# RFM69_USB_Gateway_0_92.net
KiCad netlist of a schematic drawn in EAGLE
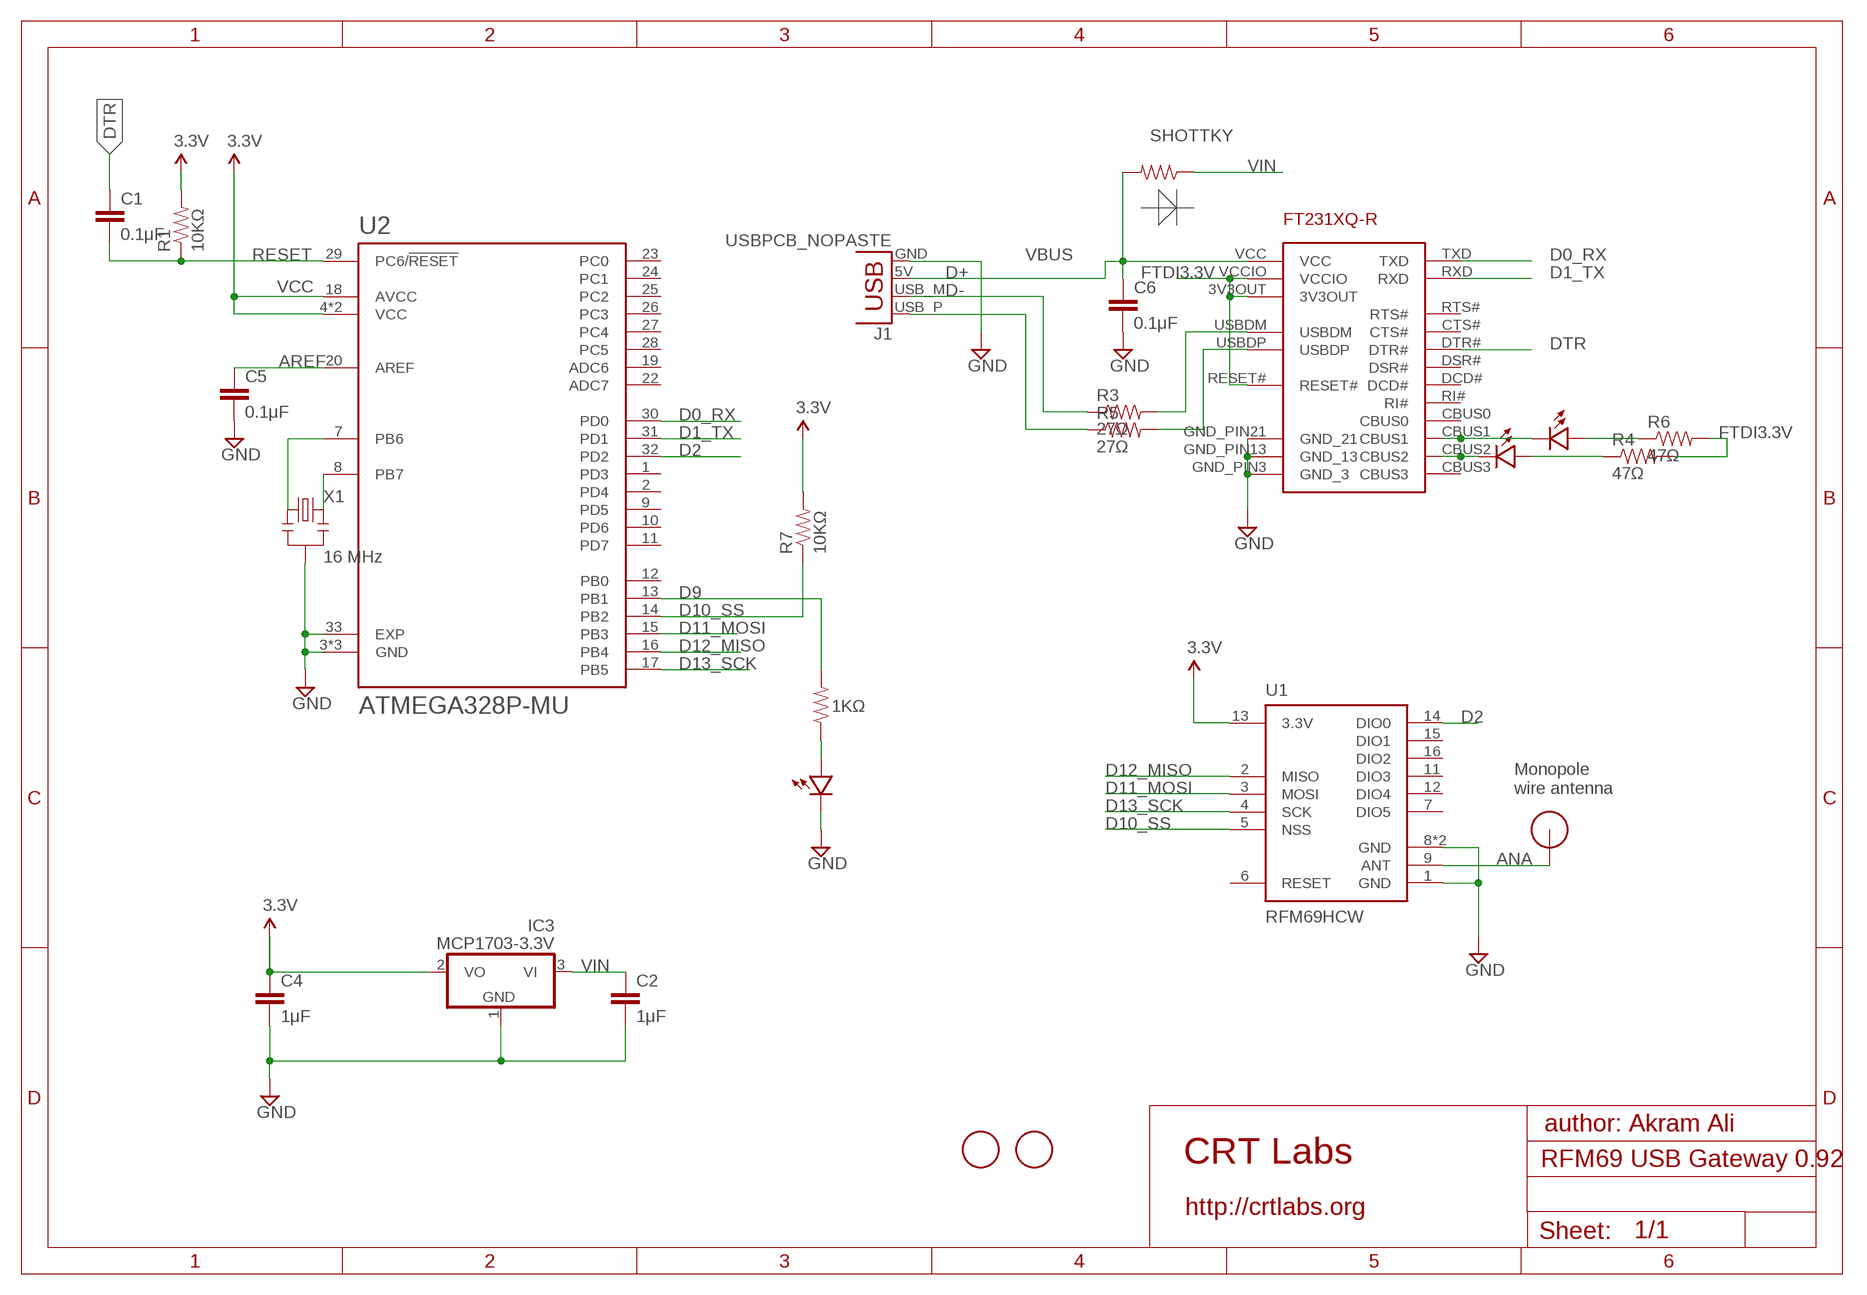
[diagram p0: schematic, sheet 1]

(export (version "E")
  (design (tool "Eeschema 10.0.6"))
  (components
    (comp (ref "C1")
      (value "0.1μF")
      (footprint "eagle-import:0805")
      (fields (field (name "MPN") "CC0805KRX7R9BB104"))
      (libsource (lib "eagle-import") (part "SparkFun_CAP0805"))
    )
    (comp (ref "C2")
      (value "1μF")
      (footprint "eagle-import:0805")
      (fields (field (name "MPN") "CC0805ZRY5V8BB105"))
      (libsource (lib "eagle-import") (part "SparkFun_CAP0805"))
    )
    (comp (ref "C4")
      (value "1μF")
      (footprint "eagle-import:0805")
      (fields (field (name "MPN") "CC0805ZRY5V8BB105"))
      (libsource (lib "eagle-import") (part "CAP0805"))
    )
    (comp (ref "C5")
      (value "0.1μF")
      (footprint "eagle-import:0805")
      (fields (field (name "MPN") "CC0805KRX7R9BB104"))
      (libsource (lib "eagle-import") (part "SparkFun_CAP0805"))
    )
    (comp (ref "C6")
      (value "0.1μF")
      (footprint "eagle-import:0805")
      (fields (field (name "MPN") "CC0805KRX7R9BB104"))
      (libsource (lib "eagle-import") (part "SparkFun_CAP0805"))
    )
    (comp (ref "D")
      (value "SHOTTKY")
      (footprint "eagle-import:0805")
      (fields (field (name "MPN") "SD0805S040S0R5"))
      (libsource (lib "eagle-import") (part "RESISTOR0805"))
    )
    (comp (ref "FT231XQ-R")
      (value "FT231XQ-R")
      (footprint "eagle-import:FTDI_FT231XQ-R_PACKAGE")
      (libsource (lib "eagle-import") (part "FT231XQ-R"))
    )
    (comp (ref "IC3")
      (value "MCP1703-3.3V")
      (footprint "eagle-import:SOT23")
      (fields (field (name "MPN") "MCP1703T-2502E/CB"))
      (libsource (lib "eagle-import") (part "MCP1703CB"))
    )
    (comp (ref "J1")
      (value "USBPCB_NOPASTE")
      (footprint "eagle-import:USB-A-PCB-NOPASTE")
      (libsource (lib "eagle-import") (part "USBPCB_NOPASTE"))
    )
    (comp (ref "R1")
      (value "10KΩ")
      (footprint "eagle-import:0805")
      (fields (field (name "MPN") "RC0805FR-0710KL"))
      (libsource (lib "eagle-import") (part "RESISTOR0805"))
    )
    (comp (ref "R2")
      (value "1KΩ")
      (footprint "eagle-import:0805")
      (fields (field (name "MPN") "RC0805FR-071KL"))
      (libsource (lib "eagle-import") (part "SparkFun_RESISTOR0805-RES"))
    )
    (comp (ref "R3")
      (value "27Ω")
      (footprint "eagle-import:0805")
      (fields (field (name "MPN") "RC0805FR-0727RL"))
      (libsource (lib "eagle-import") (part "SparkFun_RESISTOR0805-RES"))
    )
    (comp (ref "R4")
      (value "47Ω")
      (footprint "eagle-import:0805")
      (fields (field (name "MPN") "RC0805FR-0747RL "))
      (libsource (lib "eagle-import") (part "SparkFun_RESISTOR0805-RES"))
    )
    (comp (ref "R5")
      (value "27Ω")
      (footprint "eagle-import:0805")
      (fields (field (name "MPN") "RC0805FR-0727RL"))
      (libsource (lib "eagle-import") (part "SparkFun_RESISTOR0805-RES"))
    )
    (comp (ref "R6")
      (value "47Ω")
      (footprint "eagle-import:0805")
      (fields (field (name "MPN") "RC0805FR-0747RL "))
      (libsource (lib "eagle-import") (part "SparkFun_RESISTOR0805-RES"))
    )
    (comp (ref "R7")
      (value "10KΩ")
      (footprint "eagle-import:0805")
      (fields (field (name "MPN") "RC0805FR-0710KL"))
      (libsource (lib "eagle-import") (part "SparkFun_RESISTOR0805-RES"))
    )
    (comp (ref "RX")
      (value "Green")
      (footprint "eagle-import:0805-LED")
      (fields (field (name "MPN") "LG R971-KN-1"))
      (libsource (lib "eagle-import") (part "LED0805"))
    )
    (comp (ref "TX")
      (value "Red")
      (footprint "eagle-import:0805-LED")
      (fields (field (name "MPN") "LG R971-KN-1"))
      (libsource (lib "eagle-import") (part "LED0805"))
    )
    (comp (ref "U$2")
      (value "Status")
      (footprint "eagle-import:0805-LED")
      (fields (field (name "MPN") "LG R971-KN-1"))
      (libsource (lib "eagle-import") (part "LED0805"))
    )
    (comp (ref "U$3")
      (value "FIDUCIAL")
      (footprint "eagle-import:FIDUCIAL_1MM")
      (libsource (lib "eagle-import") (part "FIDUCIAL"))
    )
    (comp (ref "U$4")
      (value "FIDUCIAL")
      (footprint "eagle-import:FIDUCIAL_1MM")
      (libsource (lib "eagle-import") (part "FIDUCIAL"))
    )
    (comp (ref "U$6")
      (value "RFM12B_ANTENNA")
      (footprint "eagle-import:RFM12B-ANTENNA")
      (libsource (lib "eagle-import") (part "RFM12B_ANTENNA"))
    )
    (comp (ref "U1")
      (value "RFM69HCW")
      (footprint "eagle-import:RFM69HCW-XXXS2")
      (fields (field (name "MPN") "RFM69HW"))
      (libsource (lib "eagle-import") (part "RFM69HCW"))
    )
    (comp (ref "U2")
      (value "ATMEGA328P-MU")
      (footprint "eagle-import:QFN50P500X500X100-33N")
      (fields (field (name "MF") "Atmel") (field (name "MPN") "ATMEGA328PB-AU"))
      (libsource (lib "eagle-import") (part "ATMEGA328P-MU"))
    )
    (comp (ref "X1")
      (value "16 MHz")
      (footprint "eagle-import:RESONATOR-SMD")
      (fields (field (name "MPN") "CSTCE16M0V53-R0"))
      (libsource (lib "eagle-import") (part "RESONATORSMD"))
    )
  )
  (nets
    (net (code "1") (name "/ANA") (class "Default")
      (node (ref "U$6") (pin "P$1") (pinfunction "1_P$1") (pintype "bidirectional"))
      (node (ref "U1") (pin "9") (pinfunction "ANT_9") (pintype "passive"))
    )
    (net (code "2") (name "/AREF") (class "Default")
      (node (ref "C5") (pin "1") (pinfunction "1_1") (pintype "passive"))
      (node (ref "U2") (pin "20") (pinfunction "AREF_20") (pintype "input"))
    )
    (net (code "3") (name "/D+") (class "Default")
      (node (ref "J1") (pin "USB_P") (pinfunction "D+_USB_P") (pintype "bidirectional"))
      (node (ref "R5") (pin "1") (pinfunction "1_1") (pintype "passive"))
    )
    (net (code "4") (name "/D-") (class "Default")
      (node (ref "J1") (pin "USB_M") (pinfunction "D-_USB_M") (pintype "bidirectional"))
      (node (ref "R3") (pin "1") (pinfunction "1_1") (pintype "passive"))
    )
    (net (code "5") (name "/D0_RX") (class "Default")
      (node (ref "FT231XQ-R") (pin "TXD") (pinfunction "TXD_TXD") (pintype "bidirectional"))
      (node (ref "U2") (pin "30") (pinfunction "PD0_30") (pintype "bidirectional"))
    )
    (net (code "6") (name "/D1_TX") (class "Default")
      (node (ref "FT231XQ-R") (pin "RXD") (pinfunction "RXD_RXD") (pintype "bidirectional"))
      (node (ref "U2") (pin "31") (pinfunction "PD1_31") (pintype "bidirectional"))
    )
    (net (code "7") (name "/D2") (class "Default")
      (node (ref "U1") (pin "14") (pinfunction "DIO0_14") (pintype "bidirectional"))
      (node (ref "U2") (pin "32") (pinfunction "PD2_32") (pintype "bidirectional"))
    )
    (net (code "8") (name "/D9") (class "Default")
      (node (ref "R2") (pin "2") (pinfunction "2_2") (pintype "passive"))
      (node (ref "U2") (pin "13") (pinfunction "PB1_13") (pintype "bidirectional"))
    )
    (net (code "9") (name "/D10_SS") (class "Default")
      (node (ref "R7") (pin "1") (pinfunction "1_1") (pintype "passive"))
      (node (ref "U1") (pin "5") (pinfunction "NSS_5") (pintype "input"))
      (node (ref "U2") (pin "14") (pinfunction "PB2_14") (pintype "bidirectional"))
    )
    (net (code "10") (name "/D11_MOSI") (class "Default")
      (node (ref "U1") (pin "3") (pinfunction "MOSI_3") (pintype "input"))
      (node (ref "U2") (pin "15") (pinfunction "PB3_15") (pintype "bidirectional"))
    )
    (net (code "11") (name "/D12_MISO") (class "Default")
      (node (ref "U1") (pin "2") (pinfunction "MISO_2") (pintype "bidirectional"))
      (node (ref "U2") (pin "16") (pinfunction "PB4_16") (pintype "bidirectional"))
    )
    (net (code "12") (name "/D13_SCK") (class "Default")
      (node (ref "U1") (pin "4") (pinfunction "SCK_4") (pintype "input"))
      (node (ref "U2") (pin "17") (pinfunction "PB5_17") (pintype "bidirectional"))
    )
    (net (code "13") (name "/FTDI3.3V") (class "Default")
      (node (ref "FT231XQ-R") (pin "3V3OUT") (pinfunction "3V3OUT_3V3OUT") (pintype "bidirectional"))
      (node (ref "FT231XQ-R") (pin "RESET#") (pinfunction "RESET#_RESET#") (pintype "bidirectional"))
      (node (ref "FT231XQ-R") (pin "VCCIO") (pinfunction "VCCIO_VCCIO") (pintype "bidirectional"))
      (node (ref "R4") (pin "2") (pinfunction "2_2") (pintype "passive"))
      (node (ref "R6") (pin "2") (pinfunction "2_2") (pintype "passive"))
    )
    (net (code "14") (name "/RESET") (class "Default")
      (node (ref "C1") (pin "2") (pinfunction "2_2") (pintype "passive"))
      (node (ref "R1") (pin "1") (pinfunction "1_1") (pintype "passive"))
      (node (ref "U2") (pin "29") (pinfunction "PC6/~{RESET}_29") (pintype "bidirectional"))
    )
    (net (code "15") (name "/VBUS") (class "Default")
      (node (ref "C6") (pin "1") (pinfunction "1_1") (pintype "passive"))
      (node (ref "D") (pin "2") (pinfunction "2_2") (pintype "passive"))
      (node (ref "FT231XQ-R") (pin "VCC") (pinfunction "VCC_VCC") (pintype "bidirectional"))
      (node (ref "J1") (pin "5V") (pinfunction "VBUS_5V") (pintype "bidirectional"))
    )
    (net (code "16") (name "/VIN") (class "Default")
      (node (ref "C2") (pin "1") (pinfunction "1_1") (pintype "passive"))
      (node (ref "D") (pin "1") (pinfunction "1_1") (pintype "passive"))
      (node (ref "IC3") (pin "3") (pinfunction "VI_3") (pintype "input"))
    )
    (net (code "17") (name "3.3V") (class "Default")
      (node (ref "C4") (pin "1") (pinfunction "1_1") (pintype "passive"))
      (node (ref "IC3") (pin "2") (pinfunction "VO_2") (pintype "passive"))
      (node (ref "R1") (pin "2") (pinfunction "2_2") (pintype "passive"))
      (node (ref "R7") (pin "2") (pinfunction "2_2") (pintype "passive"))
      (node (ref "U1") (pin "13") (pinfunction "3.3V_13") (pintype "power_in"))
      (node (ref "U2") (pin "18") (pinfunction "AVCC_18") (pintype "power_in"))
      (node (ref "U2") (pin "4") (pinfunction "VCC_4") (pintype "power_in"))
      (node (ref "U2") (pin "6") (pinfunction "VCC_6") (pintype "power_in"))
    )
    (net (code "18") (name "DTR") (class "Default")
      (node (ref "C1") (pin "1") (pinfunction "1_1") (pintype "passive"))
      (node (ref "FT231XQ-R") (pin "DTR#") (pinfunction "DTR#_DTR#") (pintype "bidirectional"))
    )
    (net (code "19") (name "GND") (class "Default")
      (node (ref "C2") (pin "2") (pinfunction "2_2") (pintype "passive"))
      (node (ref "C4") (pin "2") (pinfunction "2_2") (pintype "passive"))
      (node (ref "C5") (pin "2") (pinfunction "2_2") (pintype "passive"))
      (node (ref "C6") (pin "2") (pinfunction "2_2") (pintype "passive"))
      (node (ref "FT231XQ-R") (pin "GND_PIN13") (pinfunction "GND_13_GND_PIN13") (pintype "bidirectional"))
      (node (ref "FT231XQ-R") (pin "GND_PIN21") (pinfunction "GND_21_GND_PIN21") (pintype "bidirectional"))
      (node (ref "FT231XQ-R") (pin "GND_PIN3") (pinfunction "GND_3_GND_PIN3") (pintype "bidirectional"))
      (node (ref "IC3") (pin "1") (pinfunction "GND_1") (pintype "passive"))
      (node (ref "J1") (pin "GND") (pinfunction "GND_GND") (pintype "bidirectional"))
      (node (ref "U$2") (pin "MINUS") (pinfunction "MINUS_MINUS") (pintype "passive"))
      (node (ref "U1") (pin "1") (pinfunction "GND_1") (pintype "power_in"))
      (node (ref "U1") (pin "10") (pinfunction "GND_10") (pintype "power_in"))
      (node (ref "U1") (pin "8") (pinfunction "GND_8") (pintype "power_in"))
      (node (ref "U2") (pin "21") (pinfunction "GND_21") (pintype "power_in"))
      (node (ref "U2") (pin "3") (pinfunction "GND_3") (pintype "power_in"))
      (node (ref "U2") (pin "33") (pinfunction "EXP_33") (pintype "power_in"))
      (node (ref "U2") (pin "5") (pinfunction "GND_5") (pintype "power_in"))
      (node (ref "X1") (pin "2") (pinfunction "2_2") (pintype "passive"))
    )
    (net (code "20") (name "Net-(FT231XQ-R-PadCBUS1)") (class "Default")
      (node (ref "FT231XQ-R") (pin "CBUS1") (pinfunction "CBUS1_CBUS1") (pintype "bidirectional"))
      (node (ref "RX") (pin "MINUS") (pinfunction "MINUS_MINUS") (pintype "passive"))
    )
    (net (code "21") (name "Net-(FT231XQ-R-PadCBUS2)") (class "Default")
      (node (ref "FT231XQ-R") (pin "CBUS2") (pinfunction "CBUS2_CBUS2") (pintype "bidirectional"))
      (node (ref "TX") (pin "MINUS") (pinfunction "MINUS_MINUS") (pintype "passive"))
    )
    (net (code "22") (name "Net-(FT231XQ-R-PadUSBDM)") (class "Default")
      (node (ref "FT231XQ-R") (pin "USBDM") (pinfunction "USBDM_USBDM") (pintype "bidirectional"))
      (node (ref "R3") (pin "2") (pinfunction "2_2") (pintype "passive"))
    )
    (net (code "23") (name "Net-(FT231XQ-R-PadUSBDP)") (class "Default")
      (node (ref "FT231XQ-R") (pin "USBDP") (pinfunction "USBDP_USBDP") (pintype "bidirectional"))
      (node (ref "R5") (pin "2") (pinfunction "2_2") (pintype "passive"))
    )
    (net (code "24") (name "Net-(R2-Pad1)") (class "Default")
      (node (ref "R2") (pin "1") (pinfunction "1_1") (pintype "passive"))
      (node (ref "U$2") (pin "PLUS") (pinfunction "PLUS_PLUS") (pintype "passive"))
    )
    (net (code "25") (name "Net-(R4-Pad1)") (class "Default")
      (node (ref "R4") (pin "1") (pinfunction "1_1") (pintype "passive"))
      (node (ref "TX") (pin "PLUS") (pinfunction "PLUS_PLUS") (pintype "passive"))
    )
    (net (code "26") (name "Net-(R6-Pad1)") (class "Default")
      (node (ref "R6") (pin "1") (pinfunction "1_1") (pintype "passive"))
      (node (ref "RX") (pin "PLUS") (pinfunction "PLUS_PLUS") (pintype "passive"))
    )
    (net (code "27") (name "Net-(U2-PB6)") (class "Default")
      (node (ref "U2") (pin "7") (pinfunction "PB6_7") (pintype "bidirectional"))
      (node (ref "X1") (pin "1") (pinfunction "1_1") (pintype "passive"))
    )
    (net (code "28") (name "Net-(U2-PB7)") (class "Default")
      (node (ref "U2") (pin "8") (pinfunction "PB7_8") (pintype "bidirectional"))
      (node (ref "X1") (pin "3") (pinfunction "3_3") (pintype "passive"))
    )
    (net (code "29") (name "unconnected-(FT231XQ-R-PadCBUS0)") (class "Default")
      (node (ref "FT231XQ-R") (pin "CBUS0") (pinfunction "CBUS0_CBUS0") (pintype "bidirectional"))
    )
    (net (code "30") (name "unconnected-(FT231XQ-R-PadCBUS3)") (class "Default")
      (node (ref "FT231XQ-R") (pin "CBUS3") (pinfunction "CBUS3_CBUS3") (pintype "bidirectional"))
    )
    (net (code "31") (name "unconnected-(FT231XQ-R-PadCTS#)") (class "Default")
      (node (ref "FT231XQ-R") (pin "CTS#") (pinfunction "CTS#_CTS#") (pintype "bidirectional"))
    )
    (net (code "32") (name "unconnected-(FT231XQ-R-PadDCD#)") (class "Default")
      (node (ref "FT231XQ-R") (pin "DCD#") (pinfunction "DCD#_DCD#") (pintype "bidirectional"))
    )
    (net (code "33") (name "unconnected-(FT231XQ-R-PadDSR#)") (class "Default")
      (node (ref "FT231XQ-R") (pin "DSR#") (pinfunction "DSR#_DSR#") (pintype "bidirectional"))
    )
    (net (code "34") (name "unconnected-(FT231XQ-R-PadRI#)") (class "Default")
      (node (ref "FT231XQ-R") (pin "RI#") (pinfunction "RI#_RI#") (pintype "bidirectional"))
    )
    (net (code "35") (name "unconnected-(FT231XQ-R-PadRTS#)") (class "Default")
      (node (ref "FT231XQ-R") (pin "RTS#") (pinfunction "RTS#_RTS#") (pintype "bidirectional"))
    )
    (net (code "36") (name "unconnected-(U1-DIO1-Pad15)") (class "Default")
      (node (ref "U1") (pin "15") (pinfunction "DIO1_15") (pintype "bidirectional"))
    )
    (net (code "37") (name "unconnected-(U1-DIO2-Pad16)") (class "Default")
      (node (ref "U1") (pin "16") (pinfunction "DIO2_16") (pintype "bidirectional"))
    )
    (net (code "38") (name "unconnected-(U1-DIO3-Pad11)") (class "Default")
      (node (ref "U1") (pin "11") (pinfunction "DIO3_11") (pintype "bidirectional"))
    )
    (net (code "39") (name "unconnected-(U1-DIO4-Pad12)") (class "Default")
      (node (ref "U1") (pin "12") (pinfunction "DIO4_12") (pintype "bidirectional"))
    )
    (net (code "40") (name "unconnected-(U1-DIO5-Pad7)") (class "Default")
      (node (ref "U1") (pin "7") (pinfunction "DIO5_7") (pintype "bidirectional"))
    )
    (net (code "41") (name "unconnected-(U1-RESET-Pad6)") (class "Default")
      (node (ref "U1") (pin "6") (pinfunction "RESET_6") (pintype "input"))
    )
    (net (code "42") (name "unconnected-(U2-ADC6-Pad19)") (class "Default")
      (node (ref "U2") (pin "19") (pinfunction "ADC6_19") (pintype "bidirectional"))
    )
    (net (code "43") (name "unconnected-(U2-ADC7-Pad22)") (class "Default")
      (node (ref "U2") (pin "22") (pinfunction "ADC7_22") (pintype "bidirectional"))
    )
    (net (code "44") (name "unconnected-(U2-PB0-Pad12)") (class "Default")
      (node (ref "U2") (pin "12") (pinfunction "PB0_12") (pintype "bidirectional"))
    )
    (net (code "45") (name "unconnected-(U2-PC0-Pad23)") (class "Default")
      (node (ref "U2") (pin "23") (pinfunction "PC0_23") (pintype "bidirectional"))
    )
    (net (code "46") (name "unconnected-(U2-PC1-Pad24)") (class "Default")
      (node (ref "U2") (pin "24") (pinfunction "PC1_24") (pintype "bidirectional"))
    )
    (net (code "47") (name "unconnected-(U2-PC2-Pad25)") (class "Default")
      (node (ref "U2") (pin "25") (pinfunction "PC2_25") (pintype "bidirectional"))
    )
    (net (code "48") (name "unconnected-(U2-PC3-Pad26)") (class "Default")
      (node (ref "U2") (pin "26") (pinfunction "PC3_26") (pintype "bidirectional"))
    )
    (net (code "49") (name "unconnected-(U2-PC4-Pad27)") (class "Default")
      (node (ref "U2") (pin "27") (pinfunction "PC4_27") (pintype "bidirectional"))
    )
    (net (code "50") (name "unconnected-(U2-PC5-Pad28)") (class "Default")
      (node (ref "U2") (pin "28") (pinfunction "PC5_28") (pintype "bidirectional"))
    )
    (net (code "51") (name "unconnected-(U2-PD3-Pad1)") (class "Default")
      (node (ref "U2") (pin "1") (pinfunction "PD3_1") (pintype "bidirectional"))
    )
    (net (code "52") (name "unconnected-(U2-PD4-Pad2)") (class "Default")
      (node (ref "U2") (pin "2") (pinfunction "PD4_2") (pintype "bidirectional"))
    )
    (net (code "53") (name "unconnected-(U2-PD5-Pad9)") (class "Default")
      (node (ref "U2") (pin "9") (pinfunction "PD5_9") (pintype "bidirectional"))
    )
    (net (code "54") (name "unconnected-(U2-PD6-Pad10)") (class "Default")
      (node (ref "U2") (pin "10") (pinfunction "PD6_10") (pintype "bidirectional"))
    )
    (net (code "55") (name "unconnected-(U2-PD7-Pad11)") (class "Default")
      (node (ref "U2") (pin "11") (pinfunction "PD7_11") (pintype "bidirectional"))
    )
  )
)
